# Solution_1.net
KiCad netlist of a schematic drawn in Altium Designer
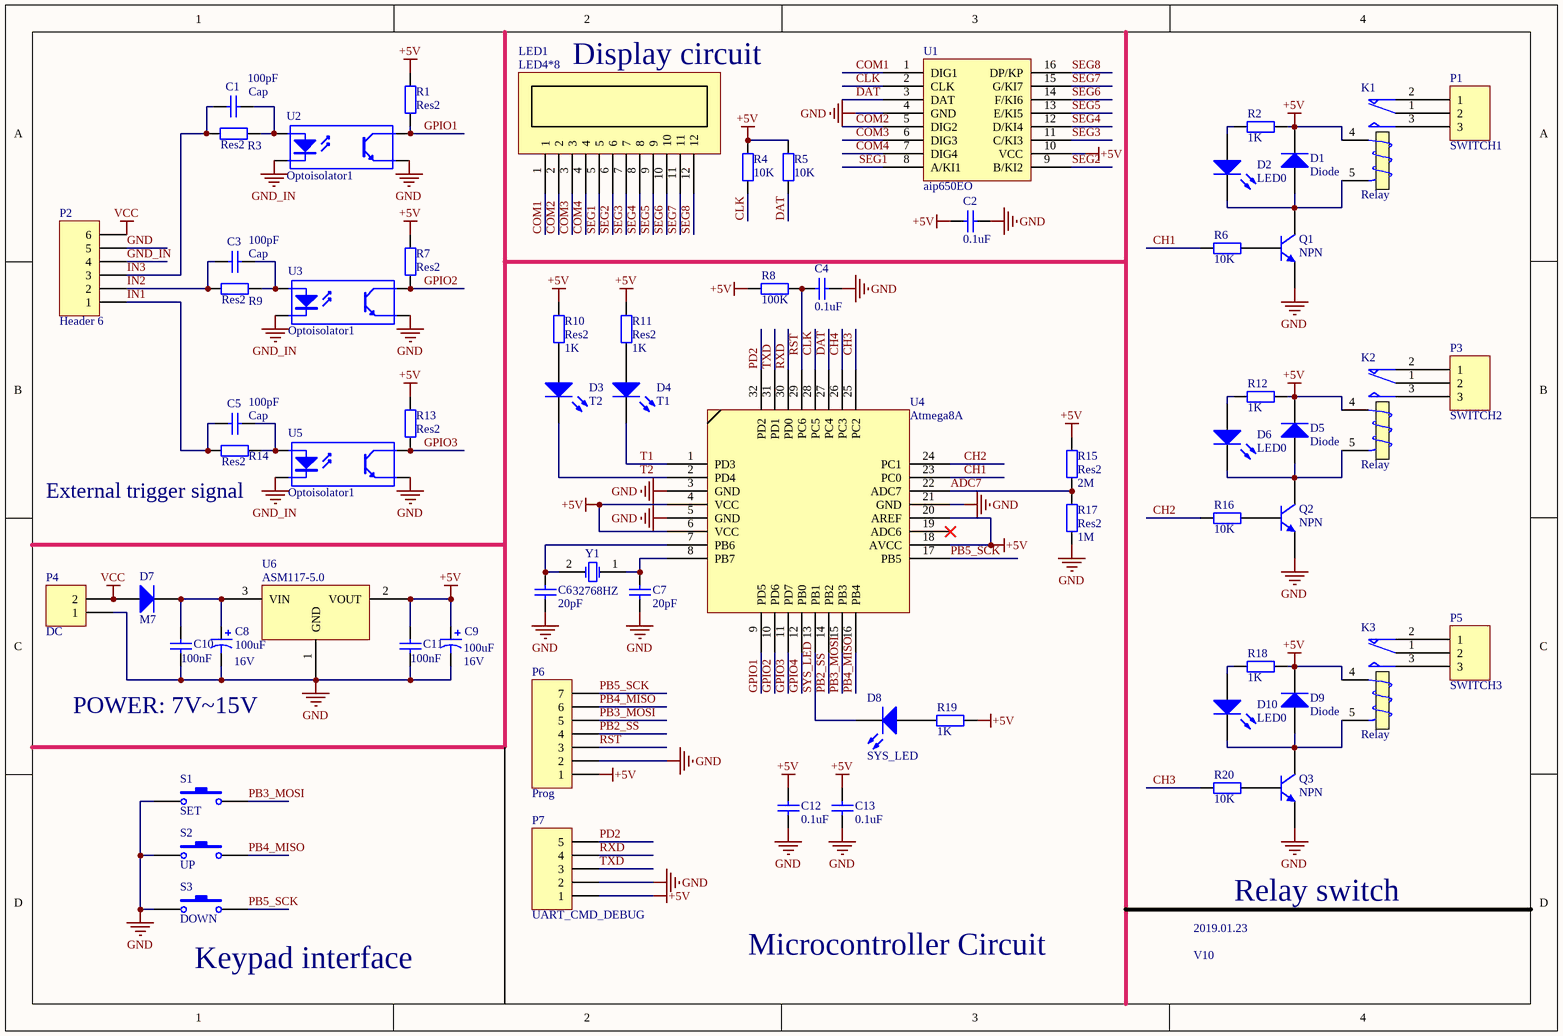
[diagram p0: Solution_1.SchDoc]

(export (version "E")
  (design (tool "Eeschema 10.0.6"))
  (components
    (comp (ref "C1")
      (value "Cap")
      (footprint "RAD-0.3")
      (description "Capacitor")
      (fields (field (name "ALTIUM_VALUE") "100pF") (field (name "PUBLISHER") "Altium Limited"))
      (libsource (lib "Miscellaneous Devices") (part "Cap"))
    )
    (comp (ref "C2")
      (value "0.1uF")
      (footprint "RAD-0.3")
      (description "Capacitor")
      (fields (field (name "PUBLISHER") "Altium Limited"))
      (libsource (lib "Miscellaneous Devices") (part "Cap"))
    )
    (comp (ref "C3")
      (value "Cap")
      (footprint "RAD-0.3")
      (description "Capacitor")
      (fields (field (name "ALTIUM_VALUE") "100pF") (field (name "PUBLISHER") "Altium Limited"))
      (libsource (lib "Miscellaneous Devices") (part "Cap"))
    )
    (comp (ref "C4")
      (value "0.1uF")
      (footprint "RAD-0.3")
      (description "Capacitor")
      (fields (field (name "PUBLISHER") "Altium Limited"))
      (libsource (lib "Miscellaneous Devices") (part "Cap"))
    )
    (comp (ref "C5")
      (value "Cap")
      (footprint "RAD-0.3")
      (description "Capacitor")
      (fields (field (name "ALTIUM_VALUE") "100pF") (field (name "PUBLISHER") "Altium Limited"))
      (libsource (lib "Miscellaneous Devices") (part "Cap"))
    )
    (comp (ref "C6")
      (value "20pF")
      (footprint "RAD-0.3")
      (description "Capacitor")
      (fields (field (name "PUBLISHER") "Altium Limited"))
      (libsource (lib "Miscellaneous Devices") (part "Cap"))
    )
    (comp (ref "C7")
      (value "20pF")
      (footprint "RAD-0.3")
      (description "Capacitor")
      (fields (field (name "PUBLISHER") "Altium Limited"))
      (libsource (lib "Miscellaneous Devices") (part "Cap"))
    )
    (comp (ref "C8")
      (value "100uF")
      (footprint "C0805")
      (description "Polarized Capacitor (Surface Mount)")
      (fields (field (name "ALTIUM_VALUE") "16V") (field (name "PUBLISHER") "Altium Limited"))
      (libsource (lib "Miscellaneous Devices") (part "Cap Pol3"))
    )
    (comp (ref "C9")
      (value "100uF")
      (footprint "C0805")
      (description "Polarized Capacitor (Surface Mount)")
      (fields (field (name "ALTIUM_VALUE") "16V") (field (name "PUBLISHER") "Altium Limited"))
      (libsource (lib "Miscellaneous Devices") (part "Cap Pol3"))
    )
    (comp (ref "C10")
      (value "100nF")
      (footprint "RAD-0.3")
      (description "Capacitor")
      (fields (field (name "PUBLISHER") "Altium Limited"))
      (libsource (lib "Miscellaneous Devices") (part "Cap"))
    )
    (comp (ref "C11")
      (value "100nF")
      (footprint "RAD-0.3")
      (description "Capacitor")
      (fields (field (name "PUBLISHER") "Altium Limited"))
      (libsource (lib "Miscellaneous Devices") (part "Cap"))
    )
    (comp (ref "C12")
      (value "0.1uF")
      (footprint "RAD-0.3")
      (description "Capacitor")
      (fields (field (name "PUBLISHER") "Altium Limited"))
      (libsource (lib "Miscellaneous Devices") (part "Cap"))
    )
    (comp (ref "C13")
      (value "0.1uF")
      (footprint "RAD-0.3")
      (description "Capacitor")
      (fields (field (name "PUBLISHER") "Altium Limited"))
      (libsource (lib "Miscellaneous Devices") (part "Cap"))
    )
    (comp (ref "D1")
      (value "Diode")
      (footprint "SMC")
      (description "Default Diode")
      (fields (field (name "PUBLISHER") "Altium Limited"))
      (libsource (lib "Miscellaneous Devices") (part "Diode"))
    )
    (comp (ref "D2")
      (value "LED0")
      (footprint "LED-0")
      (description "Typical INFRARED GaAs LED")
      (fields (field (name "PUBLISHER") "Altium Limited"))
      (libsource (lib "Miscellaneous Devices") (part "LED0"))
    )
    (comp (ref "D3")
      (value "T2")
      (footprint "LED-0")
      (description "Typical INFRARED GaAs LED")
      (fields (field (name "PUBLISHER") "Altium Limited"))
      (libsource (lib "Miscellaneous Devices") (part "LED0"))
    )
    (comp (ref "D4")
      (value "T1")
      (footprint "LED-0")
      (description "Typical INFRARED GaAs LED")
      (fields (field (name "PUBLISHER") "Altium Limited"))
      (libsource (lib "Miscellaneous Devices") (part "LED0"))
    )
    (comp (ref "D5")
      (value "Diode")
      (footprint "SMC")
      (description "Default Diode")
      (fields (field (name "PUBLISHER") "Altium Limited"))
      (libsource (lib "Miscellaneous Devices") (part "Diode"))
    )
    (comp (ref "D6")
      (value "LED0")
      (footprint "LED-0")
      (description "Typical INFRARED GaAs LED")
      (fields (field (name "PUBLISHER") "Altium Limited"))
      (libsource (lib "Miscellaneous Devices") (part "LED0"))
    )
    (comp (ref "D7")
      (value "M7")
      (footprint "SMC")
      (description "Default Diode")
      (fields (field (name "PUBLISHER") "Altium Limited"))
      (libsource (lib "Miscellaneous Devices") (part "Diode"))
    )
    (comp (ref "D8")
      (value "SYS_LED")
      (footprint "LED-0")
      (description "Typical INFRARED GaAs LED")
      (fields (field (name "PUBLISHER") "Altium Limited"))
      (libsource (lib "Miscellaneous Devices") (part "LED0"))
    )
    (comp (ref "D9")
      (value "Diode")
      (footprint "SMC")
      (description "Default Diode")
      (fields (field (name "PUBLISHER") "Altium Limited"))
      (libsource (lib "Miscellaneous Devices") (part "Diode"))
    )
    (comp (ref "D10")
      (value "LED0")
      (footprint "LED-0")
      (description "Typical INFRARED GaAs LED")
      (fields (field (name "PUBLISHER") "Altium Limited"))
      (libsource (lib "Miscellaneous Devices") (part "LED0"))
    )
    (comp (ref "K1")
      (value "Relay")
      (footprint "MODULE5B")
      (description "SPDT Relay")
      (fields (field (name "PUBLISHER") "Altium Limited"))
      (libsource (lib "Miscellaneous Devices") (part "Relay"))
    )
    (comp (ref "K2")
      (value "Relay")
      (footprint "MODULE5B")
      (description "SPDT Relay")
      (fields (field (name "PUBLISHER") "Altium Limited"))
      (libsource (lib "Miscellaneous Devices") (part "Relay"))
    )
    (comp (ref "K3")
      (value "Relay")
      (footprint "MODULE5B")
      (description "SPDT Relay")
      (fields (field (name "PUBLISHER") "Altium Limited"))
      (libsource (lib "Miscellaneous Devices") (part "Relay"))
    )
    (comp (ref "LED1")
      (value "LED4*8")
      (description "4 digital LED Displayer")
      (libsource (lib "Schlib1") (part "LED Displayer"))
    )
    (comp (ref "P1")
      (value "SWITCH1")
      (footprint "HDR1X3")
      (description "Header, 3-Pin")
      (fields (field (name "PUBLISHER") "Altium Limited"))
      (libsource (lib "Miscellaneous Connectors") (part "Header 3"))
    )
    (comp (ref "P2")
      (value "Header 6")
      (footprint "HDR1X6")
      (description "Header, 6-Pin")
      (fields (field (name "PUBLISHER") "Altium Limited"))
      (libsource (lib "Miscellaneous Connectors") (part "Header 6"))
    )
    (comp (ref "P3")
      (value "SWITCH2")
      (footprint "HDR1X3")
      (description "Header, 3-Pin")
      (fields (field (name "PUBLISHER") "Altium Limited"))
      (libsource (lib "Miscellaneous Connectors") (part "Header 3"))
    )
    (comp (ref "P4")
      (value "DC")
      (footprint "HDR1X2")
      (description "Header, 2-Pin")
      (fields (field (name "PUBLISHER") "Altium Limited"))
      (libsource (lib "Miscellaneous Connectors") (part "Header 2"))
    )
    (comp (ref "P5")
      (value "SWITCH3")
      (footprint "HDR1X3")
      (description "Header, 3-Pin")
      (fields (field (name "PUBLISHER") "Altium Limited"))
      (libsource (lib "Miscellaneous Connectors") (part "Header 3"))
    )
    (comp (ref "P6")
      (value "Prog")
      (footprint "HDR1X7")
      (description "Header, 7-Pin")
      (fields (field (name "PUBLISHER") "Altium Limited"))
      (libsource (lib "Miscellaneous Connectors") (part "Header 7"))
    )
    (comp (ref "P7")
      (value "UART_CMD_DEBUG")
      (footprint "HDR1X5")
      (description "Header, 5-Pin")
      (fields (field (name "PUBLISHER") "Altium Limited"))
      (libsource (lib "Miscellaneous Connectors") (part "Header 5"))
    )
    (comp (ref "Q1")
      (value "NPN")
      (footprint "TO-226-AA")
      (description "NPN Bipolar Transistor")
      (fields (field (name "PUBLISHER") "Altium Limited"))
      (libsource (lib "Miscellaneous Devices") (part "NPN"))
    )
    (comp (ref "Q2")
      (value "NPN")
      (footprint "TO-226-AA")
      (description "NPN Bipolar Transistor")
      (fields (field (name "PUBLISHER") "Altium Limited"))
      (libsource (lib "Miscellaneous Devices") (part "NPN"))
    )
    (comp (ref "Q3")
      (value "NPN")
      (footprint "TO-226-AA")
      (description "NPN Bipolar Transistor")
      (fields (field (name "PUBLISHER") "Altium Limited"))
      (libsource (lib "Miscellaneous Devices") (part "NPN"))
    )
    (comp (ref "R1")
      (value "Res2")
      (footprint "AXIAL-0.4")
      (description "Resistor")
      (fields (field (name "PUBLISHER") "Altium Limited"))
      (libsource (lib "") (part "Res2_1"))
    )
    (comp (ref "R2")
      (value "1K")
      (footprint "AXIAL-0.4")
      (description "Resistor")
      (fields (field (name "PUBLISHER") "Altium Limited"))
      (libsource (lib "Miscellaneous Devices") (part "Res2"))
    )
    (comp (ref "R3")
      (value "Res2")
      (footprint "AXIAL-0.4")
      (description "Resistor")
      (fields (field (name "PUBLISHER") "Altium Limited"))
      (libsource (lib "Miscellaneous Devices") (part "Res2"))
    )
    (comp (ref "R4")
      (value "10K")
      (footprint "AXIAL-0.4")
      (description "Resistor")
      (fields (field (name "PUBLISHER") "Altium Limited"))
      (libsource (lib "") (part "Res2_1"))
    )
    (comp (ref "R5")
      (value "10K")
      (footprint "AXIAL-0.4")
      (description "Resistor")
      (fields (field (name "PUBLISHER") "Altium Limited"))
      (libsource (lib "") (part "Res2_1"))
    )
    (comp (ref "R6")
      (value "10K")
      (footprint "AXIAL-0.4")
      (description "Resistor")
      (fields (field (name "PUBLISHER") "Altium Limited"))
      (libsource (lib "Miscellaneous Devices") (part "Res2"))
    )
    (comp (ref "R7")
      (value "Res2")
      (footprint "AXIAL-0.4")
      (description "Resistor")
      (fields (field (name "PUBLISHER") "Altium Limited"))
      (libsource (lib "") (part "Res2_1"))
    )
    (comp (ref "R8")
      (value "100K")
      (footprint "AXIAL-0.4")
      (description "Resistor")
      (fields (field (name "PUBLISHER") "Altium Limited"))
      (libsource (lib "Miscellaneous Devices") (part "Res2"))
    )
    (comp (ref "R9")
      (value "Res2")
      (footprint "AXIAL-0.4")
      (description "Resistor")
      (fields (field (name "PUBLISHER") "Altium Limited"))
      (libsource (lib "Miscellaneous Devices") (part "Res2"))
    )
    (comp (ref "R10")
      (value "Res2")
      (footprint "AXIAL-0.4")
      (description "Resistor")
      (fields (field (name "ALTIUM_VALUE") "1K") (field (name "PUBLISHER") "Altium Limited"))
      (libsource (lib "") (part "Res2_1"))
    )
    (comp (ref "R11")
      (value "Res2")
      (footprint "AXIAL-0.4")
      (description "Resistor")
      (fields (field (name "ALTIUM_VALUE") "1K") (field (name "PUBLISHER") "Altium Limited"))
      (libsource (lib "") (part "Res2_1"))
    )
    (comp (ref "R12")
      (value "1K")
      (footprint "AXIAL-0.4")
      (description "Resistor")
      (fields (field (name "PUBLISHER") "Altium Limited"))
      (libsource (lib "Miscellaneous Devices") (part "Res2"))
    )
    (comp (ref "R13")
      (value "Res2")
      (footprint "AXIAL-0.4")
      (description "Resistor")
      (fields (field (name "PUBLISHER") "Altium Limited"))
      (libsource (lib "") (part "Res2_1"))
    )
    (comp (ref "R14")
      (value "Res2")
      (footprint "AXIAL-0.4")
      (description "Resistor")
      (fields (field (name "PUBLISHER") "Altium Limited"))
      (libsource (lib "Miscellaneous Devices") (part "Res2"))
    )
    (comp (ref "R15")
      (value "Res2")
      (footprint "AXIAL-0.4")
      (description "Resistor")
      (fields (field (name "ALTIUM_VALUE") "2M") (field (name "PUBLISHER") "Altium Limited"))
      (libsource (lib "") (part "Res2_1"))
    )
    (comp (ref "R16")
      (value "10K")
      (footprint "AXIAL-0.4")
      (description "Resistor")
      (fields (field (name "PUBLISHER") "Altium Limited"))
      (libsource (lib "Miscellaneous Devices") (part "Res2"))
    )
    (comp (ref "R17")
      (value "Res2")
      (footprint "AXIAL-0.4")
      (description "Resistor")
      (fields (field (name "ALTIUM_VALUE") "1M") (field (name "PUBLISHER") "Altium Limited"))
      (libsource (lib "") (part "Res2_1"))
    )
    (comp (ref "R18")
      (value "1K")
      (footprint "AXIAL-0.4")
      (description "Resistor")
      (fields (field (name "PUBLISHER") "Altium Limited"))
      (libsource (lib "Miscellaneous Devices") (part "Res2"))
    )
    (comp (ref "R19")
      (value "1K")
      (footprint "AXIAL-0.4")
      (description "Resistor")
      (fields (field (name "PUBLISHER") "Altium Limited"))
      (libsource (lib "Miscellaneous Devices") (part "Res2"))
    )
    (comp (ref "R20")
      (value "10K")
      (footprint "AXIAL-0.4")
      (description "Resistor")
      (fields (field (name "PUBLISHER") "Altium Limited"))
      (libsource (lib "Miscellaneous Devices") (part "Res2"))
    )
    (comp (ref "S1")
      (value "SET")
      (footprint "SPST-2")
      (description "Switch")
      (fields (field (name "PUBLISHER") "Altium Limited"))
      (libsource (lib "Miscellaneous Devices") (part "SW-PB"))
    )
    (comp (ref "S2")
      (value "UP")
      (footprint "SPST-2")
      (description "Switch")
      (fields (field (name "PUBLISHER") "Altium Limited"))
      (libsource (lib "Miscellaneous Devices") (part "SW-PB"))
    )
    (comp (ref "S3")
      (value "DOWN")
      (footprint "SPST-2")
      (description "Switch")
      (fields (field (name "PUBLISHER") "Altium Limited"))
      (libsource (lib "Miscellaneous Devices") (part "SW-PB"))
    )
    (comp (ref "U1")
      (value "aip650EO")
      (description "LED driver")
      (libsource (lib "Schlib1") (part "aip650Eo"))
    )
    (comp (ref "U2")
      (value "Optoisolator1")
      (footprint "DIP-4")
      (description "4-Pin Phototransistor Optocoupler")
      (fields (field (name "PUBLISHER") "Altium Limited"))
      (libsource (lib "Miscellaneous Devices") (part "Optoisolator1"))
    )
    (comp (ref "U3")
      (value "Optoisolator1")
      (footprint "DIP-4")
      (description "4-Pin Phototransistor Optocoupler")
      (fields (field (name "PUBLISHER") "Altium Limited"))
      (libsource (lib "Miscellaneous Devices") (part "Optoisolator1"))
    )
    (comp (ref "U4")
      (value "Atmega8A")
      (description "AVR 8bit microcontroller")
      (libsource (lib "Schlib1") (part "ATMEGA8A"))
    )
    (comp (ref "U5")
      (value "Optoisolator1")
      (footprint "DIP-4")
      (description "4-Pin Phototransistor Optocoupler")
      (fields (field (name "PUBLISHER") "Altium Limited"))
      (libsource (lib "Miscellaneous Devices") (part "Optoisolator1"))
    )
    (comp (ref "U6")
      (value "ASM117-5.0")
      (description "5V 1A LOW DROPOUT VOLTAGE REGULATOR")
      (libsource (lib "Schlib1") (part "ASM117-5.0"))
    )
    (comp (ref "Y1")
      (value "32768HZ")
      (footprint "R38")
      (description "Crystal Oscillator")
      (fields (field (name "PUBLISHER") "Altium Limited"))
      (libsource (lib "Miscellaneous Devices") (part "XTAL"))
    )
  )
  (nets
    (net (code "1") (name "+5V") (class "Default")
      (node (ref "C11") (pin "2") (pinfunction "2_2") (pintype "passive"))
      (node (ref "C12") (pin "2") (pinfunction "2_2") (pintype "passive"))
      (node (ref "C13") (pin "2") (pinfunction "2_2") (pintype "passive"))
      (node (ref "C2") (pin "2") (pinfunction "2_2") (pintype "passive"))
      (node (ref "C9") (pin "1") (pinfunction "1_1") (pintype "passive"))
      (node (ref "D1") (pin "2") (pinfunction "K_2") (pintype "passive"))
      (node (ref "D5") (pin "2") (pinfunction "K_2") (pintype "passive"))
      (node (ref "D9") (pin "2") (pinfunction "K_2") (pintype "passive"))
      (node (ref "K1") (pin "4") (pinfunction "T1_4") (pintype "passive"))
      (node (ref "K2") (pin "4") (pinfunction "T1_4") (pintype "passive"))
      (node (ref "K3") (pin "4") (pinfunction "T1_4") (pintype "passive"))
      (node (ref "P6") (pin "1") (pinfunction "1_1") (pintype "passive"))
      (node (ref "P7") (pin "1") (pinfunction "1_1") (pintype "passive"))
      (node (ref "R1") (pin "2") (pinfunction "2_2") (pintype "passive"))
      (node (ref "R10") (pin "2") (pinfunction "2_2") (pintype "passive"))
      (node (ref "R11") (pin "2") (pinfunction "2_2") (pintype "passive"))
      (node (ref "R12") (pin "2") (pinfunction "2_2") (pintype "passive"))
      (node (ref "R13") (pin "2") (pinfunction "2_2") (pintype "passive"))
      (node (ref "R15") (pin "2") (pinfunction "2_2") (pintype "passive"))
      (node (ref "R18") (pin "2") (pinfunction "2_2") (pintype "passive"))
      (node (ref "R19") (pin "2") (pinfunction "2_2") (pintype "passive"))
      (node (ref "R2") (pin "2") (pinfunction "2_2") (pintype "passive"))
      (node (ref "R4") (pin "2") (pinfunction "2_2") (pintype "passive"))
      (node (ref "R5") (pin "2") (pinfunction "2_2") (pintype "passive"))
      (node (ref "R7") (pin "2") (pinfunction "2_2") (pintype "passive"))
      (node (ref "R8") (pin "1") (pinfunction "1_1") (pintype "passive"))
      (node (ref "U1") (pin "10") (pinfunction "VCC_10") (pintype "passive"))
      (node (ref "U4") (pin "18") (pinfunction "AVCC_18") (pintype "passive"))
      (node (ref "U4") (pin "20") (pinfunction "AREF_20") (pintype "passive"))
      (node (ref "U4") (pin "4") (pinfunction "VCC_4") (pintype "passive"))
      (node (ref "U4") (pin "6") (pinfunction "VCC_6") (pintype "passive"))
      (node (ref "U6") (pin "2") (pinfunction "VOUT_2") (pintype "passive"))
    )
    (net (code "2") (name "/ADC7") (class "Default")
      (node (ref "R15") (pin "1") (pinfunction "1_1") (pintype "passive"))
      (node (ref "R17") (pin "2") (pinfunction "2_2") (pintype "passive"))
      (node (ref "U4") (pin "22") (pinfunction "ADC7_22") (pintype "passive"))
    )
    (net (code "3") (name "/CH1") (class "Default")
      (node (ref "R6") (pin "1") (pinfunction "1_1") (pintype "passive"))
      (node (ref "U4") (pin "23") (pinfunction "PC0_23") (pintype "passive"))
    )
    (net (code "4") (name "/CH2") (class "Default")
      (node (ref "R16") (pin "1") (pinfunction "1_1") (pintype "passive"))
      (node (ref "U4") (pin "24") (pinfunction "PC1_24") (pintype "passive"))
    )
    (net (code "5") (name "/CH3") (class "Default")
      (node (ref "R20") (pin "1") (pinfunction "1_1") (pintype "passive"))
      (node (ref "U4") (pin "25") (pinfunction "PC2_25") (pintype "passive"))
    )
    (net (code "6") (name "/CH4") (class "Default")
      (node (ref "U4") (pin "26") (pinfunction "PC3_26") (pintype "passive"))
    )
    (net (code "7") (name "/CLK") (class "Default")
      (node (ref "R4") (pin "1") (pinfunction "1_1") (pintype "passive"))
      (node (ref "U1") (pin "2") (pinfunction "CLK_2") (pintype "passive"))
      (node (ref "U4") (pin "28") (pinfunction "PC5_28") (pintype "passive"))
    )
    (net (code "8") (name "/COM1") (class "Default")
      (node (ref "LED1") (pin "1") (pinfunction "1_1") (pintype "passive"))
      (node (ref "U1") (pin "1") (pinfunction "DIG1_1") (pintype "passive"))
    )
    (net (code "9") (name "/COM2") (class "Default")
      (node (ref "LED1") (pin "2") (pinfunction "2_2") (pintype "passive"))
      (node (ref "U1") (pin "5") (pinfunction "DIG2_5") (pintype "passive"))
    )
    (net (code "10") (name "/COM3") (class "Default")
      (node (ref "LED1") (pin "3") (pinfunction "3_3") (pintype "passive"))
      (node (ref "U1") (pin "6") (pinfunction "DIG3_6") (pintype "passive"))
    )
    (net (code "11") (name "/COM4") (class "Default")
      (node (ref "LED1") (pin "4") (pinfunction "4_4") (pintype "passive"))
      (node (ref "U1") (pin "7") (pinfunction "DIG4_7") (pintype "passive"))
    )
    (net (code "12") (name "/DAT") (class "Default")
      (node (ref "R5") (pin "1") (pinfunction "1_1") (pintype "passive"))
      (node (ref "U1") (pin "3") (pinfunction "DAT_3") (pintype "passive"))
      (node (ref "U4") (pin "27") (pinfunction "PC4_27") (pintype "passive"))
    )
    (net (code "13") (name "/GPIO1") (class "Default")
      (node (ref "R1") (pin "1") (pinfunction "1_1") (pintype "passive"))
      (node (ref "U2") (pin "4") (pinfunction "C_4") (pintype "passive"))
      (node (ref "U4") (pin "9") (pinfunction "PD5_9") (pintype "passive"))
    )
    (net (code "14") (name "/GPIO2") (class "Default")
      (node (ref "R7") (pin "1") (pinfunction "1_1") (pintype "passive"))
      (node (ref "U3") (pin "4") (pinfunction "C_4") (pintype "passive"))
      (node (ref "U4") (pin "10") (pinfunction "PD6_10") (pintype "passive"))
    )
    (net (code "15") (name "/GPIO3") (class "Default")
      (node (ref "R13") (pin "1") (pinfunction "1_1") (pintype "passive"))
      (node (ref "U4") (pin "11") (pinfunction "PD7_11") (pintype "passive"))
      (node (ref "U5") (pin "4") (pinfunction "C_4") (pintype "passive"))
    )
    (net (code "16") (name "/GPIO4") (class "Default")
      (node (ref "U4") (pin "12") (pinfunction "PB0_12") (pintype "passive"))
    )
    (net (code "17") (name "/IN1") (class "Default")
      (node (ref "C5") (pin "1") (pinfunction "1_1") (pintype "passive"))
      (node (ref "P2") (pin "1") (pinfunction "1_1") (pintype "passive"))
      (node (ref "R14") (pin "1") (pinfunction "1_1") (pintype "passive"))
    )
    (net (code "18") (name "/IN2") (class "Default")
      (node (ref "C3") (pin "1") (pinfunction "1_1") (pintype "passive"))
      (node (ref "P2") (pin "2") (pinfunction "2_2") (pintype "passive"))
      (node (ref "R9") (pin "1") (pinfunction "1_1") (pintype "passive"))
    )
    (net (code "19") (name "/IN3") (class "Default")
      (node (ref "C1") (pin "1") (pinfunction "1_1") (pintype "passive"))
      (node (ref "P2") (pin "3") (pinfunction "3_3") (pintype "passive"))
      (node (ref "R3") (pin "1") (pinfunction "1_1") (pintype "passive"))
    )
    (net (code "20") (name "/PB2_SS") (class "Default")
      (node (ref "P6") (pin "4") (pinfunction "4_4") (pintype "passive"))
      (node (ref "U4") (pin "14") (pinfunction "PB2_14") (pintype "passive"))
    )
    (net (code "21") (name "/PB3_MOSI") (class "Default")
      (node (ref "P6") (pin "5") (pinfunction "5_5") (pintype "passive"))
      (node (ref "S1") (pin "2") (pinfunction "2_2") (pintype "passive"))
      (node (ref "U4") (pin "15") (pinfunction "PB3_15") (pintype "passive"))
    )
    (net (code "22") (name "/PB4_MISO") (class "Default")
      (node (ref "P6") (pin "6") (pinfunction "6_6") (pintype "passive"))
      (node (ref "S2") (pin "2") (pinfunction "2_2") (pintype "passive"))
      (node (ref "U4") (pin "16") (pinfunction "PB4_16") (pintype "passive"))
    )
    (net (code "23") (name "/PB5_SCK") (class "Default")
      (node (ref "P6") (pin "7") (pinfunction "7_7") (pintype "passive"))
      (node (ref "S3") (pin "2") (pinfunction "2_2") (pintype "passive"))
      (node (ref "U4") (pin "17") (pinfunction "PB5_17") (pintype "passive"))
    )
    (net (code "24") (name "/PD2") (class "Default")
      (node (ref "P7") (pin "5") (pinfunction "5_5") (pintype "passive"))
      (node (ref "U4") (pin "32") (pinfunction "PD2_32") (pintype "passive"))
    )
    (net (code "25") (name "/RST") (class "Default")
      (node (ref "C4") (pin "2") (pinfunction "2_2") (pintype "passive"))
      (node (ref "P6") (pin "3") (pinfunction "3_3") (pintype "passive"))
      (node (ref "R8") (pin "2") (pinfunction "2_2") (pintype "passive"))
      (node (ref "U4") (pin "29") (pinfunction "PC6_29") (pintype "passive"))
    )
    (net (code "26") (name "/RXD") (class "Default")
      (node (ref "P7") (pin "4") (pinfunction "4_4") (pintype "passive"))
      (node (ref "U4") (pin "30") (pinfunction "PD0_30") (pintype "passive"))
    )
    (net (code "27") (name "/SEG1") (class "Default")
      (node (ref "LED1") (pin "5") (pinfunction "5_5") (pintype "passive"))
      (node (ref "U1") (pin "8") (pinfunction "A/KI1_8") (pintype "passive"))
    )
    (net (code "28") (name "/SEG2") (class "Default")
      (node (ref "LED1") (pin "6") (pinfunction "6_6") (pintype "passive"))
      (node (ref "U1") (pin "9") (pinfunction "B/KI2_9") (pintype "passive"))
    )
    (net (code "29") (name "/SEG3") (class "Default")
      (node (ref "LED1") (pin "7") (pinfunction "7_7") (pintype "passive"))
      (node (ref "U1") (pin "11") (pinfunction "C/KI3_11") (pintype "passive"))
    )
    (net (code "30") (name "/SEG4") (class "Default")
      (node (ref "LED1") (pin "8") (pinfunction "8_8") (pintype "passive"))
      (node (ref "U1") (pin "12") (pinfunction "D/KI4_12") (pintype "passive"))
    )
    (net (code "31") (name "/SEG5") (class "Default")
      (node (ref "LED1") (pin "9") (pinfunction "9_9") (pintype "passive"))
      (node (ref "U1") (pin "13") (pinfunction "E/KI5_13") (pintype "passive"))
    )
    (net (code "32") (name "/SEG6") (class "Default")
      (node (ref "LED1") (pin "10") (pinfunction "10_10") (pintype "passive"))
      (node (ref "U1") (pin "14") (pinfunction "F/KI6_14") (pintype "passive"))
    )
    (net (code "33") (name "/SEG7") (class "Default")
      (node (ref "LED1") (pin "11") (pinfunction "11_11") (pintype "passive"))
      (node (ref "U1") (pin "15") (pinfunction "G/KI7_15") (pintype "passive"))
    )
    (net (code "34") (name "/SEG8") (class "Default")
      (node (ref "LED1") (pin "12") (pinfunction "12_12") (pintype "passive"))
      (node (ref "U1") (pin "16") (pinfunction "DP/KP_16") (pintype "passive"))
    )
    (net (code "35") (name "/SYS_LED") (class "Default")
      (node (ref "D8") (pin "2") (pinfunction "K_2") (pintype "passive"))
      (node (ref "U4") (pin "13") (pinfunction "PB1_13") (pintype "passive"))
    )
    (net (code "36") (name "/T1") (class "Default")
      (node (ref "D4") (pin "2") (pinfunction "K_2") (pintype "passive"))
      (node (ref "U4") (pin "1") (pinfunction "PD3_1") (pintype "passive"))
    )
    (net (code "37") (name "/T2") (class "Default")
      (node (ref "D3") (pin "2") (pinfunction "K_2") (pintype "passive"))
      (node (ref "U4") (pin "2") (pinfunction "PD4_2") (pintype "passive"))
    )
    (net (code "38") (name "/TXD") (class "Default")
      (node (ref "P7") (pin "3") (pinfunction "3_3") (pintype "passive"))
      (node (ref "U4") (pin "31") (pinfunction "PD1_31") (pintype "passive"))
    )
    (net (code "39") (name "GND") (class "Default")
      (node (ref "C10") (pin "1") (pinfunction "1_1") (pintype "passive"))
      (node (ref "C11") (pin "1") (pinfunction "1_1") (pintype "passive"))
      (node (ref "C12") (pin "1") (pinfunction "1_1") (pintype "passive"))
      (node (ref "C13") (pin "1") (pinfunction "1_1") (pintype "passive"))
      (node (ref "C2") (pin "1") (pinfunction "1_1") (pintype "passive"))
      (node (ref "C4") (pin "1") (pinfunction "1_1") (pintype "passive"))
      (node (ref "C6") (pin "1") (pinfunction "1_1") (pintype "passive"))
      (node (ref "C7") (pin "1") (pinfunction "1_1") (pintype "passive"))
      (node (ref "C8") (pin "2") (pinfunction "2_2") (pintype "passive"))
      (node (ref "C9") (pin "2") (pinfunction "2_2") (pintype "passive"))
      (node (ref "P2") (pin "5") (pinfunction "5_5") (pintype "passive"))
      (node (ref "P4") (pin "1") (pinfunction "1_1") (pintype "passive"))
      (node (ref "P6") (pin "2") (pinfunction "2_2") (pintype "passive"))
      (node (ref "P7") (pin "2") (pinfunction "2_2") (pintype "passive"))
      (node (ref "Q1") (pin "3") (pinfunction "E_3") (pintype "passive"))
      (node (ref "Q2") (pin "3") (pinfunction "E_3") (pintype "passive"))
      (node (ref "Q3") (pin "3") (pinfunction "E_3") (pintype "passive"))
      (node (ref "R17") (pin "1") (pinfunction "1_1") (pintype "passive"))
      (node (ref "S1") (pin "1") (pinfunction "1_1") (pintype "passive"))
      (node (ref "S2") (pin "1") (pinfunction "1_1") (pintype "passive"))
      (node (ref "S3") (pin "1") (pinfunction "1_1") (pintype "passive"))
      (node (ref "U1") (pin "4") (pinfunction "GND_4") (pintype "passive"))
      (node (ref "U2") (pin "3") (pinfunction "E_3") (pintype "passive"))
      (node (ref "U3") (pin "3") (pinfunction "E_3") (pintype "passive"))
      (node (ref "U4") (pin "21") (pinfunction "GND_21") (pintype "passive"))
      (node (ref "U4") (pin "3") (pinfunction "GND_3") (pintype "passive"))
      (node (ref "U4") (pin "5") (pinfunction "GND_5") (pintype "passive"))
      (node (ref "U5") (pin "3") (pinfunction "E_3") (pintype "passive"))
      (node (ref "U6") (pin "1") (pinfunction "GND_1") (pintype "passive"))
    )
    (net (code "40") (name "GND_IN") (class "Default")
      (node (ref "P2") (pin "4") (pinfunction "4_4") (pintype "passive"))
      (node (ref "U2") (pin "2") (pinfunction "K_2") (pintype "passive"))
      (node (ref "U3") (pin "2") (pinfunction "K_2") (pintype "passive"))
      (node (ref "U5") (pin "2") (pinfunction "K_2") (pintype "passive"))
    )
    (net (code "41") (name "Net-(D1-A)") (class "Default")
      (node (ref "D1") (pin "1") (pinfunction "A_1") (pintype "passive"))
      (node (ref "D2") (pin "2") (pinfunction "K_2") (pintype "passive"))
      (node (ref "K1") (pin "5") (pinfunction "T2_5") (pintype "passive"))
      (node (ref "Q1") (pin "1") (pinfunction "C_1") (pintype "passive"))
    )
    (net (code "42") (name "Net-(D2-A)") (class "Default")
      (node (ref "D2") (pin "1") (pinfunction "A_1") (pintype "passive"))
      (node (ref "R2") (pin "1") (pinfunction "1_1") (pintype "passive"))
    )
    (net (code "43") (name "Net-(D3-A)") (class "Default")
      (node (ref "D3") (pin "1") (pinfunction "A_1") (pintype "passive"))
      (node (ref "R10") (pin "1") (pinfunction "1_1") (pintype "passive"))
    )
    (net (code "44") (name "Net-(D4-A)") (class "Default")
      (node (ref "D4") (pin "1") (pinfunction "A_1") (pintype "passive"))
      (node (ref "R11") (pin "1") (pinfunction "1_1") (pintype "passive"))
    )
    (net (code "45") (name "Net-(D5-A)") (class "Default")
      (node (ref "D5") (pin "1") (pinfunction "A_1") (pintype "passive"))
      (node (ref "D6") (pin "2") (pinfunction "K_2") (pintype "passive"))
      (node (ref "K2") (pin "5") (pinfunction "T2_5") (pintype "passive"))
      (node (ref "Q2") (pin "1") (pinfunction "C_1") (pintype "passive"))
    )
    (net (code "46") (name "Net-(D6-A)") (class "Default")
      (node (ref "D6") (pin "1") (pinfunction "A_1") (pintype "passive"))
      (node (ref "R12") (pin "1") (pinfunction "1_1") (pintype "passive"))
    )
    (net (code "47") (name "Net-(D7-K)") (class "Default")
      (node (ref "C10") (pin "2") (pinfunction "2_2") (pintype "passive"))
      (node (ref "C8") (pin "1") (pinfunction "1_1") (pintype "passive"))
      (node (ref "D7") (pin "2") (pinfunction "K_2") (pintype "passive"))
      (node (ref "U6") (pin "3") (pinfunction "VIN_3") (pintype "passive"))
    )
    (net (code "48") (name "Net-(D8-A)") (class "Default")
      (node (ref "D8") (pin "1") (pinfunction "A_1") (pintype "passive"))
      (node (ref "R19") (pin "1") (pinfunction "1_1") (pintype "passive"))
    )
    (net (code "49") (name "Net-(D10-A)") (class "Default")
      (node (ref "D10") (pin "1") (pinfunction "A_1") (pintype "passive"))
      (node (ref "R18") (pin "1") (pinfunction "1_1") (pintype "passive"))
    )
    (net (code "50") (name "Net-(D10-K)") (class "Default")
      (node (ref "D10") (pin "2") (pinfunction "K_2") (pintype "passive"))
      (node (ref "D9") (pin "1") (pinfunction "A_1") (pintype "passive"))
      (node (ref "K3") (pin "5") (pinfunction "T2_5") (pintype "passive"))
      (node (ref "Q3") (pin "1") (pinfunction "C_1") (pintype "passive"))
    )
    (net (code "51") (name "Net-(K1-COM)") (class "Default")
      (node (ref "K1") (pin "1") (pinfunction "COM_1") (pintype "passive"))
      (node (ref "P1") (pin "2") (pinfunction "2_2") (pintype "passive"))
    )
    (net (code "52") (name "Net-(K1-NC)") (class "Default")
      (node (ref "K1") (pin "2") (pinfunction "NC_2") (pintype "passive"))
      (node (ref "P1") (pin "1") (pinfunction "1_1") (pintype "passive"))
    )
    (net (code "53") (name "Net-(K1-NO)") (class "Default")
      (node (ref "K1") (pin "3") (pinfunction "NO_3") (pintype "passive"))
      (node (ref "P1") (pin "3") (pinfunction "3_3") (pintype "passive"))
    )
    (net (code "54") (name "Net-(K2-COM)") (class "Default")
      (node (ref "K2") (pin "1") (pinfunction "COM_1") (pintype "passive"))
      (node (ref "P3") (pin "2") (pinfunction "2_2") (pintype "passive"))
    )
    (net (code "55") (name "Net-(K2-NC)") (class "Default")
      (node (ref "K2") (pin "2") (pinfunction "NC_2") (pintype "passive"))
      (node (ref "P3") (pin "1") (pinfunction "1_1") (pintype "passive"))
    )
    (net (code "56") (name "Net-(K2-NO)") (class "Default")
      (node (ref "K2") (pin "3") (pinfunction "NO_3") (pintype "passive"))
      (node (ref "P3") (pin "3") (pinfunction "3_3") (pintype "passive"))
    )
    (net (code "57") (name "Net-(K3-COM)") (class "Default")
      (node (ref "K3") (pin "1") (pinfunction "COM_1") (pintype "passive"))
      (node (ref "P5") (pin "2") (pinfunction "2_2") (pintype "passive"))
    )
    (net (code "58") (name "Net-(K3-NC)") (class "Default")
      (node (ref "K3") (pin "2") (pinfunction "NC_2") (pintype "passive"))
      (node (ref "P5") (pin "1") (pinfunction "1_1") (pintype "passive"))
    )
    (net (code "59") (name "Net-(K3-NO)") (class "Default")
      (node (ref "K3") (pin "3") (pinfunction "NO_3") (pintype "passive"))
      (node (ref "P5") (pin "3") (pinfunction "3_3") (pintype "passive"))
    )
    (net (code "60") (name "Net-(Q1-B)") (class "Default")
      (node (ref "Q1") (pin "2") (pinfunction "B_2") (pintype "passive"))
      (node (ref "R6") (pin "2") (pinfunction "2_2") (pintype "passive"))
    )
    (net (code "61") (name "Net-(Q2-B)") (class "Default")
      (node (ref "Q2") (pin "2") (pinfunction "B_2") (pintype "passive"))
      (node (ref "R16") (pin "2") (pinfunction "2_2") (pintype "passive"))
    )
    (net (code "62") (name "Net-(Q3-B)") (class "Default")
      (node (ref "Q3") (pin "2") (pinfunction "B_2") (pintype "passive"))
      (node (ref "R20") (pin "2") (pinfunction "2_2") (pintype "passive"))
    )
    (net (code "63") (name "Net-(U2-A)") (class "Default")
      (node (ref "C1") (pin "2") (pinfunction "2_2") (pintype "passive"))
      (node (ref "R3") (pin "2") (pinfunction "2_2") (pintype "passive"))
      (node (ref "U2") (pin "1") (pinfunction "A_1") (pintype "passive"))
    )
    (net (code "64") (name "Net-(U3-A)") (class "Default")
      (node (ref "C3") (pin "2") (pinfunction "2_2") (pintype "passive"))
      (node (ref "R9") (pin "2") (pinfunction "2_2") (pintype "passive"))
      (node (ref "U3") (pin "1") (pinfunction "A_1") (pintype "passive"))
    )
    (net (code "65") (name "Net-(U4-PB6)") (class "Default")
      (node (ref "C6") (pin "2") (pinfunction "2_2") (pintype "passive"))
      (node (ref "U4") (pin "7") (pinfunction "PB6_7") (pintype "passive"))
      (node (ref "Y1") (pin "2") (pinfunction "OSC2_2") (pintype "passive"))
    )
    (net (code "66") (name "Net-(U4-PB7)") (class "Default")
      (node (ref "C7") (pin "2") (pinfunction "2_2") (pintype "passive"))
      (node (ref "U4") (pin "8") (pinfunction "PB7_8") (pintype "passive"))
      (node (ref "Y1") (pin "1") (pinfunction "OSC1_1") (pintype "passive"))
    )
    (net (code "67") (name "Net-(U5-A)") (class "Default")
      (node (ref "C5") (pin "2") (pinfunction "2_2") (pintype "passive"))
      (node (ref "R14") (pin "2") (pinfunction "2_2") (pintype "passive"))
      (node (ref "U5") (pin "1") (pinfunction "A_1") (pintype "passive"))
    )
    (net (code "68") (name "VCC") (class "Default")
      (node (ref "D7") (pin "1") (pinfunction "A_1") (pintype "passive"))
      (node (ref "P2") (pin "6") (pinfunction "6_6") (pintype "passive"))
      (node (ref "P4") (pin "2") (pinfunction "2_2") (pintype "passive"))
    )
    (net (code "69") (name "unconnected-(U4-ADC6-Pad19)") (class "Default")
      (node (ref "U4") (pin "19") (pinfunction "ADC6_19") (pintype "passive+no_connect"))
    )
  )
)
